# SCFschem.net
KiCad netlist of a schematic drawn in EAGLE
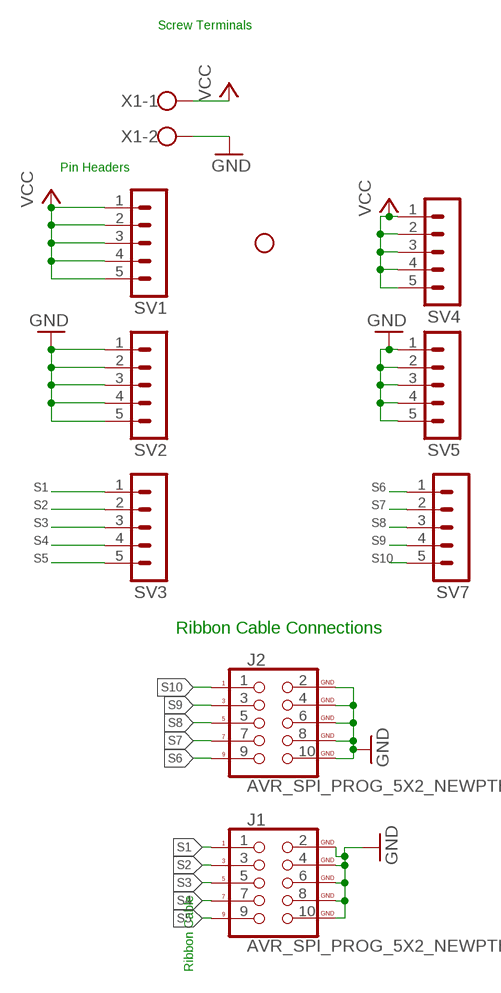
[diagram p0: schematic, sheet 1]

(export (version "E")
  (design (tool "Eeschema 10.0.6"))
  (components
    (comp (ref "H1")
      (value "STAND-OFF")
      (footprint "eagle-import:STAND-OFF")
      (libsource (lib "eagle-import") (part "STAND-OFF"))
    )
    (comp (ref "J1")
      (value "AVR_SPI_PROG_5X2_NEWPTH2")
      (footprint "eagle-import:2X5-SHROUDED")
      (libsource (lib "eagle-import") (part "AVR_SPI_PROG_5X2_NEWPTH2"))
    )
    (comp (ref "J2")
      (value "AVR_SPI_PROG_5X2_NEWPTH2")
      (footprint "eagle-import:2X5-SHROUDED")
      (libsource (lib "eagle-import") (part "AVR_SPI_PROG_5X2_NEWPTH2"))
    )
    (comp (ref "SV1")
      (value "MA05-1")
      (footprint "eagle-import:MA05-1")
      (libsource (lib "eagle-import") (part "MA05-1"))
    )
    (comp (ref "SV2")
      (value "MA05-1")
      (footprint "eagle-import:MA05-1")
      (libsource (lib "eagle-import") (part "MA05-1"))
    )
    (comp (ref "SV3")
      (value "MA05-1")
      (footprint "eagle-import:MA05-1")
      (libsource (lib "eagle-import") (part "MA05-1"))
    )
    (comp (ref "SV4")
      (value "MA05-1")
      (footprint "eagle-import:MA05-1")
      (libsource (lib "eagle-import") (part "MA05-1"))
    )
    (comp (ref "SV5")
      (value "MA05-1")
      (footprint "eagle-import:MA05-1")
      (libsource (lib "eagle-import") (part "MA05-1"))
    )
    (comp (ref "SV7")
      (value "MA05-1")
      (footprint "eagle-import:MA05-1")
      (libsource (lib "eagle-import") (part "MA05-1"))
    )
    (comp (ref "X1")
      (value "1X02_5MM_SCREW")
      (footprint "eagle-import:W237-102")
      (fields (field (name "MPN") "237-102"))
      (libsource (lib "eagle-import") (part "1X02_5MM_SCREW"))
    )
  )
  (nets
    (net (code "1") (name "GND") (class "Default")
      (node (ref "J1") (pin "10") (pinfunction "GND_10") (pintype "power_in"))
      (node (ref "J1") (pin "2") (pinfunction "GND_2") (pintype "power_in"))
      (node (ref "J1") (pin "4") (pinfunction "GND_4") (pintype "power_in"))
      (node (ref "J1") (pin "6") (pinfunction "GND_6") (pintype "power_in"))
      (node (ref "J1") (pin "8") (pinfunction "GND_8") (pintype "power_in"))
      (node (ref "J2") (pin "10") (pinfunction "GND_10") (pintype "power_in"))
      (node (ref "J2") (pin "2") (pinfunction "GND_2") (pintype "power_in"))
      (node (ref "J2") (pin "4") (pinfunction "GND_4") (pintype "power_in"))
      (node (ref "J2") (pin "6") (pinfunction "GND_6") (pintype "power_in"))
      (node (ref "J2") (pin "8") (pinfunction "GND_8") (pintype "power_in"))
      (node (ref "SV2") (pin "1") (pinfunction "1_1") (pintype "passive"))
      (node (ref "SV2") (pin "2") (pinfunction "2_2") (pintype "passive"))
      (node (ref "SV2") (pin "3") (pinfunction "3_3") (pintype "passive"))
      (node (ref "SV2") (pin "4") (pinfunction "4_4") (pintype "passive"))
      (node (ref "SV2") (pin "5") (pinfunction "5_5") (pintype "passive"))
      (node (ref "SV5") (pin "1") (pinfunction "1_1") (pintype "passive"))
      (node (ref "SV5") (pin "2") (pinfunction "2_2") (pintype "passive"))
      (node (ref "SV5") (pin "3") (pinfunction "3_3") (pintype "passive"))
      (node (ref "SV5") (pin "4") (pinfunction "4_4") (pintype "passive"))
      (node (ref "SV5") (pin "5") (pinfunction "5_5") (pintype "passive"))
      (node (ref "X1") (pin "2") (pinfunction "KL_2") (pintype "passive"))
    )
    (net (code "2") (name "S1") (class "Default")
      (node (ref "J1") (pin "1") (pinfunction "1_1") (pintype "passive"))
      (node (ref "SV3") (pin "1") (pinfunction "1_1") (pintype "passive"))
    )
    (net (code "3") (name "S2") (class "Default")
      (node (ref "J1") (pin "3") (pinfunction "3_3") (pintype "passive"))
      (node (ref "SV3") (pin "2") (pinfunction "2_2") (pintype "passive"))
    )
    (net (code "4") (name "S3") (class "Default")
      (node (ref "J1") (pin "5") (pinfunction "5_5") (pintype "passive"))
      (node (ref "SV3") (pin "3") (pinfunction "3_3") (pintype "passive"))
    )
    (net (code "5") (name "S4") (class "Default")
      (node (ref "J1") (pin "7") (pinfunction "7_7") (pintype "passive"))
      (node (ref "SV3") (pin "4") (pinfunction "4_4") (pintype "passive"))
    )
    (net (code "6") (name "S5") (class "Default")
      (node (ref "J1") (pin "9") (pinfunction "9_9") (pintype "passive"))
      (node (ref "SV3") (pin "5") (pinfunction "5_5") (pintype "passive"))
    )
    (net (code "7") (name "S6") (class "Default")
      (node (ref "J2") (pin "9") (pinfunction "9_9") (pintype "passive"))
      (node (ref "SV7") (pin "1") (pinfunction "1_1") (pintype "passive"))
    )
    (net (code "8") (name "S7") (class "Default")
      (node (ref "J2") (pin "7") (pinfunction "7_7") (pintype "passive"))
      (node (ref "SV7") (pin "2") (pinfunction "2_2") (pintype "passive"))
    )
    (net (code "9") (name "S8") (class "Default")
      (node (ref "J2") (pin "5") (pinfunction "5_5") (pintype "passive"))
      (node (ref "SV7") (pin "3") (pinfunction "3_3") (pintype "passive"))
    )
    (net (code "10") (name "S9") (class "Default")
      (node (ref "J2") (pin "3") (pinfunction "3_3") (pintype "passive"))
      (node (ref "SV7") (pin "4") (pinfunction "4_4") (pintype "passive"))
    )
    (net (code "11") (name "S10") (class "Default")
      (node (ref "J2") (pin "1") (pinfunction "1_1") (pintype "passive"))
      (node (ref "SV7") (pin "5") (pinfunction "5_5") (pintype "passive"))
    )
    (net (code "12") (name "VCC") (class "Default")
      (node (ref "SV1") (pin "1") (pinfunction "1_1") (pintype "passive"))
      (node (ref "SV1") (pin "2") (pinfunction "2_2") (pintype "passive"))
      (node (ref "SV1") (pin "3") (pinfunction "3_3") (pintype "passive"))
      (node (ref "SV1") (pin "4") (pinfunction "4_4") (pintype "passive"))
      (node (ref "SV1") (pin "5") (pinfunction "5_5") (pintype "passive"))
      (node (ref "SV4") (pin "1") (pinfunction "1_1") (pintype "passive"))
      (node (ref "SV4") (pin "2") (pinfunction "2_2") (pintype "passive"))
      (node (ref "SV4") (pin "3") (pinfunction "3_3") (pintype "passive"))
      (node (ref "SV4") (pin "4") (pinfunction "4_4") (pintype "passive"))
      (node (ref "SV4") (pin "5") (pinfunction "5_5") (pintype "passive"))
      (node (ref "X1") (pin "1") (pinfunction "KL_1") (pintype "passive"))
    )
  )
)
